# 36.net
KiCad netlist of a schematic drawn in Altium Designer
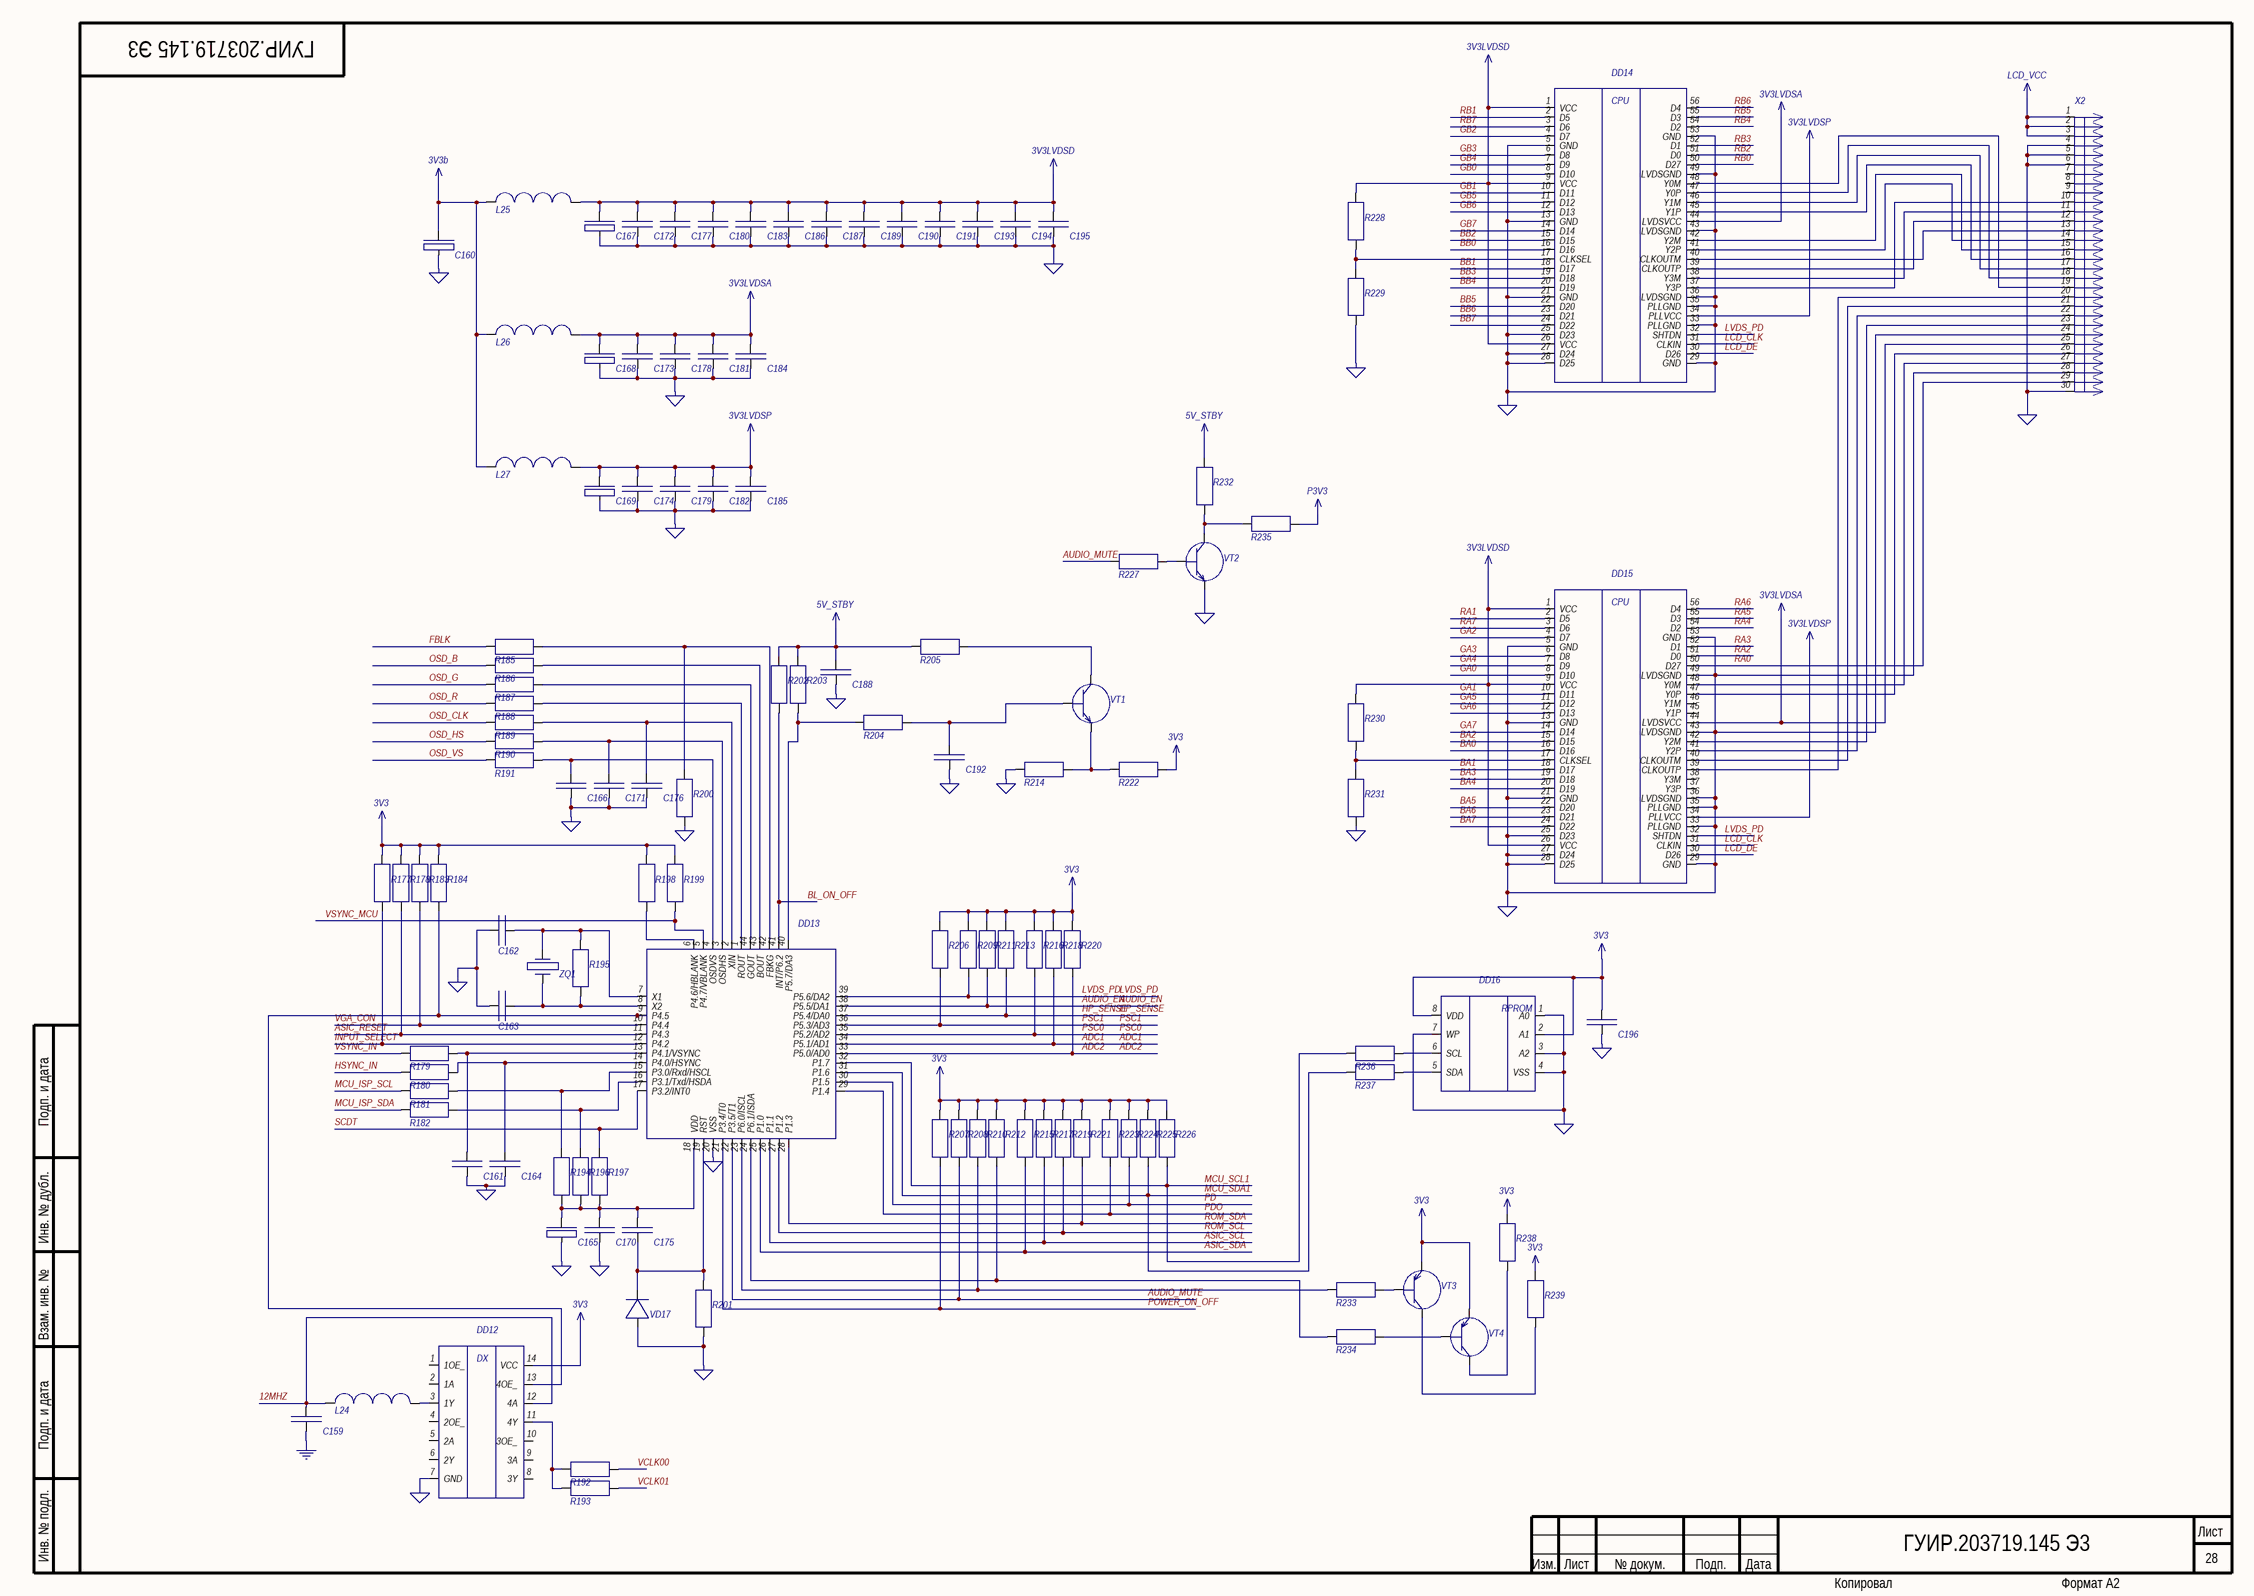
[diagram p0: 36.SchDoc]

(export (version "E")
  (design (tool "Eeschema 10.0.6"))
  (components
    (comp (ref "C159")
      (value "Capacitor")
      (footprint "cap_electro_13")
      (libsource (lib "31_lib") (part "Capacitor"))
    )
    (comp (ref "C160")
      (value "TuningCapacitor")
      (footprint "31_lib:Cap_tantal_D")
      (libsource (lib "31_lib") (part "TuningCapacitor"))
    )
    (comp (ref "C161")
      (value "Capacitor")
      (footprint "cap_electro_13")
      (libsource (lib "31_lib") (part "Capacitor"))
    )
    (comp (ref "C162")
      (value "Capacitor")
      (footprint "cap_electro_13")
      (libsource (lib "31_lib") (part "Capacitor"))
    )
    (comp (ref "C163")
      (value "Capacitor")
      (footprint "cap_electro_13")
      (libsource (lib "31_lib") (part "Capacitor"))
    )
    (comp (ref "C164")
      (value "Capacitor")
      (footprint "cap_electro_13")
      (libsource (lib "31_lib") (part "Capacitor"))
    )
    (comp (ref "C165")
      (value "TuningCapacitor")
      (footprint "31_lib:Cap_tantal_D")
      (libsource (lib "31_lib") (part "TuningCapacitor"))
    )
    (comp (ref "C166")
      (value "Capacitor")
      (footprint "cap_electro_13")
      (libsource (lib "31_lib") (part "Capacitor"))
    )
    (comp (ref "C167")
      (value "TuningCapacitor")
      (footprint "31_lib:Cap_tantal_D")
      (libsource (lib "31_lib") (part "TuningCapacitor"))
    )
    (comp (ref "C168")
      (value "TuningCapacitor")
      (footprint "31_lib:Cap_tantal_D")
      (libsource (lib "31_lib") (part "TuningCapacitor"))
    )
    (comp (ref "C169")
      (value "TuningCapacitor")
      (footprint "31_lib:Cap_tantal_D")
      (libsource (lib "31_lib") (part "TuningCapacitor"))
    )
    (comp (ref "C170")
      (value "Capacitor")
      (footprint "cap_electro_13")
      (libsource (lib "31_lib") (part "Capacitor"))
    )
    (comp (ref "C171")
      (value "Capacitor")
      (footprint "cap_electro_13")
      (libsource (lib "31_lib") (part "Capacitor"))
    )
    (comp (ref "C172")
      (value "Capacitor")
      (footprint "cap_electro_13")
      (libsource (lib "31_lib") (part "Capacitor"))
    )
    (comp (ref "C173")
      (value "Capacitor")
      (footprint "cap_electro_13")
      (libsource (lib "31_lib") (part "Capacitor"))
    )
    (comp (ref "C174")
      (value "Capacitor")
      (footprint "cap_electro_13")
      (libsource (lib "31_lib") (part "Capacitor"))
    )
    (comp (ref "C175")
      (value "Capacitor")
      (footprint "cap_electro_13")
      (libsource (lib "31_lib") (part "Capacitor"))
    )
    (comp (ref "C176")
      (value "Capacitor")
      (footprint "cap_electro_13")
      (libsource (lib "31_lib") (part "Capacitor"))
    )
    (comp (ref "C177")
      (value "Capacitor")
      (footprint "cap_electro_13")
      (libsource (lib "31_lib") (part "Capacitor"))
    )
    (comp (ref "C178")
      (value "Capacitor")
      (footprint "cap_electro_13")
      (libsource (lib "31_lib") (part "Capacitor"))
    )
    (comp (ref "C179")
      (value "Capacitor")
      (footprint "cap_electro_13")
      (libsource (lib "31_lib") (part "Capacitor"))
    )
    (comp (ref "C180")
      (value "Capacitor")
      (footprint "cap_electro_13")
      (libsource (lib "31_lib") (part "Capacitor"))
    )
    (comp (ref "C181")
      (value "Capacitor")
      (footprint "cap_electro_13")
      (libsource (lib "31_lib") (part "Capacitor"))
    )
    (comp (ref "C182")
      (value "Capacitor")
      (footprint "cap_electro_13")
      (libsource (lib "31_lib") (part "Capacitor"))
    )
    (comp (ref "C183")
      (value "Capacitor")
      (footprint "cap_electro_13")
      (libsource (lib "31_lib") (part "Capacitor"))
    )
    (comp (ref "C184")
      (value "Capacitor")
      (footprint "cap_electro_13")
      (libsource (lib "31_lib") (part "Capacitor"))
    )
    (comp (ref "C185")
      (value "Capacitor")
      (footprint "cap_electro_13")
      (libsource (lib "31_lib") (part "Capacitor"))
    )
    (comp (ref "C186")
      (value "Capacitor")
      (footprint "cap_electro_13")
      (libsource (lib "31_lib") (part "Capacitor"))
    )
    (comp (ref "C187")
      (value "Capacitor")
      (footprint "cap_electro_13")
      (libsource (lib "31_lib") (part "Capacitor"))
    )
    (comp (ref "C188")
      (value "Capacitor")
      (footprint "cap_electro_13")
      (libsource (lib "31_lib") (part "Capacitor"))
    )
    (comp (ref "C189")
      (value "Capacitor")
      (footprint "cap_electro_13")
      (libsource (lib "31_lib") (part "Capacitor"))
    )
    (comp (ref "C190")
      (value "Capacitor")
      (footprint "cap_electro_13")
      (libsource (lib "31_lib") (part "Capacitor"))
    )
    (comp (ref "C191")
      (value "Capacitor")
      (footprint "cap_electro_13")
      (libsource (lib "31_lib") (part "Capacitor"))
    )
    (comp (ref "C192")
      (value "Capacitor")
      (footprint "cap_electro_13")
      (libsource (lib "31_lib") (part "Capacitor"))
    )
    (comp (ref "C193")
      (value "Capacitor")
      (footprint "cap_electro_13")
      (libsource (lib "31_lib") (part "Capacitor"))
    )
    (comp (ref "C194")
      (value "Capacitor")
      (footprint "cap_electro_13")
      (libsource (lib "31_lib") (part "Capacitor"))
    )
    (comp (ref "C195")
      (value "Capacitor")
      (footprint "cap_electro_13")
      (libsource (lib "31_lib") (part "Capacitor"))
    )
    (comp (ref "C196")
      (value "Capacitor")
      (footprint "cap_electro_13")
      (libsource (lib "31_lib") (part "Capacitor"))
    )
    (comp (ref "DD12")
      (value "74LCX125")
      (footprint "31_lib:74LCX125(page12)")
      (libsource (lib "31_lib") (part "74LCX125"))
    )
    (comp (ref "DD13")
      (value "SM0230")
      (footprint "31_lib:SM0230")
      (libsource (lib "31_lib") (part "SM0230"))
    )
    (comp (ref "DD14")
      (value "SN75LVDS83")
      (footprint "31_lib:SN75LVDS83_v2")
      (libsource (lib "31_lib") (part "SN75LVDS83"))
    )
    (comp (ref "DD15")
      (value "SN75LVDS83")
      (footprint "31_lib:SN75LVDS83_v2")
      (libsource (lib "31_lib") (part "SN75LVDS83"))
    )
    (comp (ref "DD16") (value "24LC16") (footprint "31_lib:24Cxx") (libsource (lib "31_lib") (part "24LC16")))
    (comp (ref "L24")
      (value "Inductor")
      (footprint "31_lib:inductor")
      (libsource (lib "31_lib") (part "Inductor"))
    )
    (comp (ref "L25")
      (value "Inductor")
      (footprint "31_lib:inductor")
      (libsource (lib "31_lib") (part "Inductor"))
    )
    (comp (ref "L26")
      (value "Inductor")
      (footprint "31_lib:inductor")
      (libsource (lib "31_lib") (part "Inductor"))
    )
    (comp (ref "L27")
      (value "Inductor")
      (footprint "31_lib:inductor")
      (libsource (lib "31_lib") (part "Inductor"))
    )
    (comp (ref "R177")
      (value "Resistor")
      (footprint "lab_7_footprints:R_1206")
      (libsource (lib "31_lib") (part "Resistor"))
    )
    (comp (ref "R178")
      (value "Resistor")
      (footprint "lab_7_footprints:R_1206")
      (libsource (lib "31_lib") (part "Resistor"))
    )
    (comp (ref "R179")
      (value "Resistor")
      (footprint "lab_7_footprints:R_1206")
      (libsource (lib "31_lib") (part "Resistor"))
    )
    (comp (ref "R180")
      (value "Resistor")
      (footprint "lab_7_footprints:R_1206")
      (libsource (lib "31_lib") (part "Resistor"))
    )
    (comp (ref "R181")
      (value "Resistor")
      (footprint "lab_7_footprints:R_1206")
      (libsource (lib "31_lib") (part "Resistor"))
    )
    (comp (ref "R182")
      (value "Resistor")
      (footprint "lab_7_footprints:R_1206")
      (libsource (lib "31_lib") (part "Resistor"))
    )
    (comp (ref "R183")
      (value "Resistor")
      (footprint "lab_7_footprints:R_1206")
      (libsource (lib "31_lib") (part "Resistor"))
    )
    (comp (ref "R184")
      (value "Resistor")
      (footprint "lab_7_footprints:R_1206")
      (libsource (lib "31_lib") (part "Resistor"))
    )
    (comp (ref "R185")
      (value "Resistor")
      (footprint "lab_7_footprints:R_1206")
      (libsource (lib "31_lib") (part "Resistor"))
    )
    (comp (ref "R186")
      (value "Resistor")
      (footprint "lab_7_footprints:R_1206")
      (libsource (lib "31_lib") (part "Resistor"))
    )
    (comp (ref "R187")
      (value "Resistor")
      (footprint "lab_7_footprints:R_1206")
      (libsource (lib "31_lib") (part "Resistor"))
    )
    (comp (ref "R188")
      (value "Resistor")
      (footprint "lab_7_footprints:R_1206")
      (libsource (lib "31_lib") (part "Resistor"))
    )
    (comp (ref "R189")
      (value "Resistor")
      (footprint "lab_7_footprints:R_1206")
      (libsource (lib "31_lib") (part "Resistor"))
    )
    (comp (ref "R190")
      (value "Resistor")
      (footprint "lab_7_footprints:R_1206")
      (libsource (lib "31_lib") (part "Resistor"))
    )
    (comp (ref "R191")
      (value "Resistor")
      (footprint "lab_7_footprints:R_1206")
      (libsource (lib "31_lib") (part "Resistor"))
    )
    (comp (ref "R192")
      (value "Resistor")
      (footprint "lab_7_footprints:R_1206")
      (libsource (lib "31_lib") (part "Resistor"))
    )
    (comp (ref "R193")
      (value "Resistor")
      (footprint "lab_7_footprints:R_1206")
      (libsource (lib "31_lib") (part "Resistor"))
    )
    (comp (ref "R194")
      (value "Resistor")
      (footprint "lab_7_footprints:R_1206")
      (libsource (lib "31_lib") (part "Resistor"))
    )
    (comp (ref "R195")
      (value "Resistor")
      (footprint "lab_7_footprints:R_1206")
      (libsource (lib "31_lib") (part "Resistor"))
    )
    (comp (ref "R196")
      (value "Resistor")
      (footprint "lab_7_footprints:R_1206")
      (libsource (lib "31_lib") (part "Resistor"))
    )
    (comp (ref "R197")
      (value "Resistor")
      (footprint "lab_7_footprints:R_1206")
      (libsource (lib "31_lib") (part "Resistor"))
    )
    (comp (ref "R198")
      (value "Resistor")
      (footprint "lab_7_footprints:R_1206")
      (libsource (lib "31_lib") (part "Resistor"))
    )
    (comp (ref "R199")
      (value "Resistor")
      (footprint "lab_7_footprints:R_1206")
      (libsource (lib "31_lib") (part "Resistor"))
    )
    (comp (ref "R200")
      (value "Resistor")
      (footprint "lab_7_footprints:R_1206")
      (libsource (lib "31_lib") (part "Resistor"))
    )
    (comp (ref "R201")
      (value "Resistor")
      (footprint "lab_7_footprints:R_1206")
      (libsource (lib "31_lib") (part "Resistor"))
    )
    (comp (ref "R202")
      (value "Resistor")
      (footprint "lab_7_footprints:R_1206")
      (libsource (lib "31_lib") (part "Resistor"))
    )
    (comp (ref "R203")
      (value "Resistor")
      (footprint "lab_7_footprints:R_1206")
      (libsource (lib "31_lib") (part "Resistor"))
    )
    (comp (ref "R204")
      (value "Resistor")
      (footprint "lab_7_footprints:R_1206")
      (libsource (lib "31_lib") (part "Resistor"))
    )
    (comp (ref "R205")
      (value "Resistor")
      (footprint "lab_7_footprints:R_1206")
      (libsource (lib "31_lib") (part "Resistor"))
    )
    (comp (ref "R206")
      (value "Resistor")
      (footprint "lab_7_footprints:R_1206")
      (libsource (lib "31_lib") (part "Resistor"))
    )
    (comp (ref "R207")
      (value "Resistor")
      (footprint "lab_7_footprints:R_1206")
      (libsource (lib "31_lib") (part "Resistor"))
    )
    (comp (ref "R208")
      (value "Resistor")
      (footprint "lab_7_footprints:R_1206")
      (libsource (lib "31_lib") (part "Resistor"))
    )
    (comp (ref "R209")
      (value "Resistor")
      (footprint "lab_7_footprints:R_1206")
      (libsource (lib "31_lib") (part "Resistor"))
    )
    (comp (ref "R210")
      (value "Resistor")
      (footprint "lab_7_footprints:R_1206")
      (libsource (lib "31_lib") (part "Resistor"))
    )
    (comp (ref "R211")
      (value "Resistor")
      (footprint "lab_7_footprints:R_1206")
      (libsource (lib "31_lib") (part "Resistor"))
    )
    (comp (ref "R212")
      (value "Resistor")
      (footprint "lab_7_footprints:R_1206")
      (libsource (lib "31_lib") (part "Resistor"))
    )
    (comp (ref "R213")
      (value "Resistor")
      (footprint "lab_7_footprints:R_1206")
      (libsource (lib "31_lib") (part "Resistor"))
    )
    (comp (ref "R214")
      (value "Resistor")
      (footprint "lab_7_footprints:R_1206")
      (libsource (lib "31_lib") (part "Resistor"))
    )
    (comp (ref "R215")
      (value "Resistor")
      (footprint "lab_7_footprints:R_1206")
      (libsource (lib "31_lib") (part "Resistor"))
    )
    (comp (ref "R216")
      (value "Resistor")
      (footprint "lab_7_footprints:R_1206")
      (libsource (lib "31_lib") (part "Resistor"))
    )
    (comp (ref "R217")
      (value "Resistor")
      (footprint "lab_7_footprints:R_1206")
      (libsource (lib "31_lib") (part "Resistor"))
    )
    (comp (ref "R218")
      (value "Resistor")
      (footprint "lab_7_footprints:R_1206")
      (libsource (lib "31_lib") (part "Resistor"))
    )
    (comp (ref "R219")
      (value "Resistor")
      (footprint "lab_7_footprints:R_1206")
      (libsource (lib "31_lib") (part "Resistor"))
    )
    (comp (ref "R220")
      (value "Resistor")
      (footprint "lab_7_footprints:R_1206")
      (libsource (lib "31_lib") (part "Resistor"))
    )
    (comp (ref "R221")
      (value "Resistor")
      (footprint "lab_7_footprints:R_1206")
      (libsource (lib "31_lib") (part "Resistor"))
    )
    (comp (ref "R222")
      (value "Resistor")
      (footprint "lab_7_footprints:R_1206")
      (libsource (lib "31_lib") (part "Resistor"))
    )
    (comp (ref "R223")
      (value "Resistor")
      (footprint "lab_7_footprints:R_1206")
      (libsource (lib "31_lib") (part "Resistor"))
    )
    (comp (ref "R224")
      (value "Resistor")
      (footprint "lab_7_footprints:R_1206")
      (libsource (lib "31_lib") (part "Resistor"))
    )
    (comp (ref "R225")
      (value "Resistor")
      (footprint "lab_7_footprints:R_1206")
      (libsource (lib "31_lib") (part "Resistor"))
    )
    (comp (ref "R226")
      (value "Resistor")
      (footprint "lab_7_footprints:R_1206")
      (libsource (lib "31_lib") (part "Resistor"))
    )
    (comp (ref "R227")
      (value "Resistor")
      (footprint "lab_7_footprints:R_1206")
      (libsource (lib "31_lib") (part "Resistor"))
    )
    (comp (ref "R228")
      (value "Resistor")
      (footprint "lab_7_footprints:R_1206")
      (libsource (lib "31_lib") (part "Resistor"))
    )
    (comp (ref "R229")
      (value "Resistor")
      (footprint "lab_7_footprints:R_1206")
      (libsource (lib "31_lib") (part "Resistor"))
    )
    (comp (ref "R230")
      (value "Resistor")
      (footprint "lab_7_footprints:R_1206")
      (libsource (lib "31_lib") (part "Resistor"))
    )
    (comp (ref "R231")
      (value "Resistor")
      (footprint "lab_7_footprints:R_1206")
      (libsource (lib "31_lib") (part "Resistor"))
    )
    (comp (ref "R232")
      (value "Resistor")
      (footprint "lab_7_footprints:R_1206")
      (libsource (lib "31_lib") (part "Resistor"))
    )
    (comp (ref "R233")
      (value "Resistor")
      (footprint "lab_7_footprints:R_1206")
      (libsource (lib "31_lib") (part "Resistor"))
    )
    (comp (ref "R234")
      (value "Resistor")
      (footprint "lab_7_footprints:R_1206")
      (libsource (lib "31_lib") (part "Resistor"))
    )
    (comp (ref "R235")
      (value "Resistor")
      (footprint "lab_7_footprints:R_1206")
      (libsource (lib "31_lib") (part "Resistor"))
    )
    (comp (ref "R236")
      (value "Resistor")
      (footprint "lab_7_footprints:R_1206")
      (libsource (lib "31_lib") (part "Resistor"))
    )
    (comp (ref "R237")
      (value "Resistor")
      (footprint "lab_7_footprints:R_1206")
      (libsource (lib "31_lib") (part "Resistor"))
    )
    (comp (ref "R238")
      (value "Resistor")
      (footprint "lab_7_footprints:R_1206")
      (libsource (lib "31_lib") (part "Resistor"))
    )
    (comp (ref "R239")
      (value "Resistor")
      (footprint "lab_7_footprints:R_1206")
      (libsource (lib "31_lib") (part "Resistor"))
    )
    (comp (ref "VD17")
      (value "Diode")
      (footprint "lab_7_footprints:zener_diode")
      (libsource (lib "31_lib") (part "Diode"))
    )
    (comp (ref "VT1")
      (value "MMBT3904L")
      (footprint "31_lib:MMBT3904L")
      (libsource (lib "31_lib") (part "MMBT3904L"))
    )
    (comp (ref "VT2")
      (value "MMBT3904L")
      (footprint "31_lib:MMBT3904L")
      (libsource (lib "31_lib") (part "MMBT3904L"))
    )
    (comp (ref "VT3") (value "2N3906") (footprint "31_lib:2N3906") (libsource (lib "31_lib") (part "2N3906")))
    (comp (ref "VT4") (value "2N3906") (footprint "31_lib:2N3906") (libsource (lib "31_lib") (part "2N3906")))
    (comp (ref "X2")
      (value "FI-SE30P-HF")
      (footprint "31_lib:FI-SE30P-HF_v2")
      (libsource (lib "31_lib") (part "FI-SE30P-HF"))
    )
    (comp (ref "ZQ1")
      (value "Crystal")
      (footprint "lab_7_footprints:crystal")
      (libsource (lib "31_lib") (part "Crystal"))
    )
  )
  (nets
    (net (code "1") (name "/12MHZ") (class "Default")
      (node (ref "C159") (pin "1") (pinfunction "1_1") (pintype "passive"))
      (node (ref "DD12") (pin "12") (pinfunction "4A_12") (pintype "passive"))
      (node (ref "L24") (pin "1") (pinfunction "1_1") (pintype "passive"))
    )
    (net (code "2") (name "/ADC1") (class "Default")
      (node (ref "DD13") (pin "34") (pinfunction "P5.1/AD1_34") (pintype "passive"))
      (node (ref "R218") (pin "2") (pinfunction "2_2") (pintype "passive"))
    )
    (net (code "3") (name "/ADC2") (class "Default")
      (node (ref "DD13") (pin "33") (pinfunction "P5.0/AD0_33") (pintype "passive"))
      (node (ref "R220") (pin "2") (pinfunction "2_2") (pintype "passive"))
    )
    (net (code "4") (name "/ASIC_RESET") (class "Default")
      (node (ref "DD13") (pin "11") (pinfunction "P4.3_11") (pintype "passive"))
      (node (ref "R178") (pin "1") (pinfunction "1_1") (pintype "passive"))
    )
    (net (code "5") (name "/ASIC_SCL") (class "Default")
      (node (ref "DD13") (pin "26") (pinfunction "P1.1_26") (pintype "passive"))
      (node (ref "R217") (pin "2") (pinfunction "2_2") (pintype "passive"))
    )
    (net (code "6") (name "/ASIC_SDA") (class "Default")
      (node (ref "DD13") (pin "25") (pinfunction "P1.0_25") (pintype "passive"))
      (node (ref "R215") (pin "2") (pinfunction "2_2") (pintype "passive"))
    )
    (net (code "7") (name "/AUDIO_EN") (class "Default")
      (node (ref "DD13") (pin "38") (pinfunction "P5.5/DA1_38") (pintype "passive"))
      (node (ref "R211") (pin "2") (pinfunction "2_2") (pintype "passive"))
    )
    (net (code "8") (name "/AUDIO_MUTE") (class "Default")
      (node (ref "DD13") (pin "22") (pinfunction "P3.5/T1_22") (pintype "passive"))
      (node (ref "R208") (pin "2") (pinfunction "2_2") (pintype "passive"))
      (node (ref "R227") (pin "1") (pinfunction "1_1") (pintype "passive"))
    )
    (net (code "9") (name "/BA0") (class "Default")
      (node (ref "DD15") (pin "16") (pinfunction "D16_16") (pintype "passive"))
    )
    (net (code "10") (name "/BA1") (class "Default")
      (node (ref "DD15") (pin "18") (pinfunction "D17_18") (pintype "passive"))
    )
    (net (code "11") (name "/BA2") (class "Default")
      (node (ref "DD15") (pin "15") (pinfunction "D15_15") (pintype "passive"))
    )
    (net (code "12") (name "/BA3") (class "Default")
      (node (ref "DD15") (pin "19") (pinfunction "D18_19") (pintype "passive"))
    )
    (net (code "13") (name "/BA4") (class "Default")
      (node (ref "DD15") (pin "20") (pinfunction "D19_20") (pintype "passive"))
    )
    (net (code "14") (name "/BA5") (class "Default")
      (node (ref "DD15") (pin "22") (pinfunction "D20_22") (pintype "passive"))
    )
    (net (code "15") (name "/BA6") (class "Default")
      (node (ref "DD15") (pin "23") (pinfunction "D21_23") (pintype "passive"))
    )
    (net (code "16") (name "/BA7") (class "Default")
      (node (ref "DD15") (pin "24") (pinfunction "D22_24") (pintype "passive"))
    )
    (net (code "17") (name "/BB0") (class "Default")
      (node (ref "DD14") (pin "16") (pinfunction "D16_16") (pintype "passive"))
    )
    (net (code "18") (name "/BB1") (class "Default")
      (node (ref "DD14") (pin "18") (pinfunction "D17_18") (pintype "passive"))
    )
    (net (code "19") (name "/BB2") (class "Default")
      (node (ref "DD14") (pin "15") (pinfunction "D15_15") (pintype "passive"))
    )
    (net (code "20") (name "/BB3") (class "Default")
      (node (ref "DD14") (pin "19") (pinfunction "D18_19") (pintype "passive"))
    )
    (net (code "21") (name "/BB4") (class "Default")
      (node (ref "DD14") (pin "20") (pinfunction "D19_20") (pintype "passive"))
    )
    (net (code "22") (name "/BB5") (class "Default")
      (node (ref "DD14") (pin "22") (pinfunction "D20_22") (pintype "passive"))
    )
    (net (code "23") (name "/BB6") (class "Default")
      (node (ref "DD14") (pin "23") (pinfunction "D21_23") (pintype "passive"))
    )
    (net (code "24") (name "/BB7") (class "Default")
      (node (ref "DD14") (pin "24") (pinfunction "D22_24") (pintype "passive"))
    )
    (net (code "25") (name "/BL_ON_OFF") (class "Default")
      (node (ref "DD13") (pin "41") (pinfunction "INT/P6.2_41") (pintype "passive"))
      (node (ref "R202") (pin "2") (pinfunction "2_2") (pintype "passive"))
    )
    (net (code "26") (name "/FBLK") (class "Default")
      (node (ref "R185") (pin "2") (pinfunction "2_2") (pintype "passive"))
    )
    (net (code "27") (name "/GA0") (class "Default")
      (node (ref "DD15") (pin "8") (pinfunction "D10_8") (pintype "passive"))
    )
    (net (code "28") (name "/GA1") (class "Default")
      (node (ref "DD15") (pin "10") (pinfunction "D11_10") (pintype "passive"))
    )
    (net (code "29") (name "/GA2") (class "Default")
      (node (ref "DD15") (pin "4") (pinfunction "D7_4") (pintype "passive"))
    )
    (net (code "30") (name "/GA3") (class "Default")
      (node (ref "DD15") (pin "6") (pinfunction "D8_6") (pintype "passive"))
    )
    (net (code "31") (name "/GA4") (class "Default")
      (node (ref "DD15") (pin "7") (pinfunction "D9_7") (pintype "passive"))
    )
    (net (code "32") (name "/GA5") (class "Default")
      (node (ref "DD15") (pin "11") (pinfunction "D12_11") (pintype "passive"))
    )
    (net (code "33") (name "/GA6") (class "Default")
      (node (ref "DD15") (pin "12") (pinfunction "D13_12") (pintype "passive"))
    )
    (net (code "34") (name "/GA7") (class "Default")
      (node (ref "DD15") (pin "14") (pinfunction "D14_14") (pintype "passive"))
    )
    (net (code "35") (name "/GB0") (class "Default")
      (node (ref "DD14") (pin "8") (pinfunction "D10_8") (pintype "passive"))
    )
    (net (code "36") (name "/GB1") (class "Default")
      (node (ref "DD14") (pin "10") (pinfunction "D11_10") (pintype "passive"))
    )
    (net (code "37") (name "/GB2") (class "Default")
      (node (ref "DD14") (pin "4") (pinfunction "D7_4") (pintype "passive"))
    )
    (net (code "38") (name "/GB3") (class "Default")
      (node (ref "DD14") (pin "6") (pinfunction "D8_6") (pintype "passive"))
    )
    (net (code "39") (name "/GB4") (class "Default")
      (node (ref "DD14") (pin "7") (pinfunction "D9_7") (pintype "passive"))
    )
    (net (code "40") (name "/GB5") (class "Default")
      (node (ref "DD14") (pin "11") (pinfunction "D12_11") (pintype "passive"))
    )
    (net (code "41") (name "/GB6") (class "Default")
      (node (ref "DD14") (pin "12") (pinfunction "D13_12") (pintype "passive"))
    )
    (net (code "42") (name "/GB7") (class "Default")
      (node (ref "DD14") (pin "14") (pinfunction "D14_14") (pintype "passive"))
    )
    (net (code "43") (name "/HP_SENSE") (class "Default")
      (node (ref "DD13") (pin "37") (pinfunction "P5.4/DA0_37") (pintype "passive"))
      (node (ref "R213") (pin "2") (pinfunction "2_2") (pintype "passive"))
    )
    (net (code "44") (name "/HSYNC_IN") (class "Default")
      (node (ref "R180") (pin "1") (pinfunction "1_1") (pintype "passive"))
    )
    (net (code "45") (name "/INPUT_SELECT") (class "Default")
      (node (ref "DD13") (pin "12") (pinfunction "P4.2_12") (pintype "passive"))
      (node (ref "R177") (pin "1") (pinfunction "1_1") (pintype "passive"))
    )
    (net (code "46") (name "/LCD_CLK") (class "Default")
      (node (ref "DD14") (pin "31") (pinfunction "CLKIN_31") (pintype "passive"))
      (node (ref "DD15") (pin "31") (pinfunction "CLKIN_31") (pintype "passive"))
    )
    (net (code "47") (name "/LCD_DE") (class "Default")
      (node (ref "DD14") (pin "30") (pinfunction "D26_30") (pintype "passive"))
      (node (ref "DD15") (pin "30") (pinfunction "D26_30") (pintype "passive"))
    )
    (net (code "48") (name "/LVDS_PD") (class "Default")
      (node (ref "DD13") (pin "39") (pinfunction "P5.6/DA2_39") (pintype "passive"))
      (node (ref "DD14") (pin "32") (pinfunction "SHTDN_32") (pintype "passive"))
      (node (ref "DD15") (pin "32") (pinfunction "SHTDN_32") (pintype "passive"))
      (node (ref "R209") (pin "2") (pinfunction "2_2") (pintype "passive"))
    )
    (net (code "49") (name "/MCU_ISP_SCL") (class "Default")
      (node (ref "R181") (pin "1") (pinfunction "1_1") (pintype "passive"))
    )
    (net (code "50") (name "/MCU_ISP_SDA") (class "Default")
      (node (ref "R182") (pin "1") (pinfunction "1_1") (pintype "passive"))
    )
    (net (code "51") (name "/MCU_SCL1") (class "Default")
      (node (ref "DD13") (pin "32") (pinfunction "P1.7_32") (pintype "passive"))
      (node (ref "R226") (pin "2") (pinfunction "2_2") (pintype "passive"))
      (node (ref "R236") (pin "1") (pinfunction "1_1") (pintype "passive"))
    )
    (net (code "52") (name "/MCU_SDA1") (class "Default")
      (node (ref "DD13") (pin "31") (pinfunction "P1.6_31") (pintype "passive"))
      (node (ref "R225") (pin "2") (pinfunction "2_2") (pintype "passive"))
      (node (ref "R237") (pin "1") (pinfunction "1_1") (pintype "passive"))
    )
    (net (code "53") (name "/OSD_B") (class "Default")
      (node (ref "R186") (pin "2") (pinfunction "2_2") (pintype "passive"))
    )
    (net (code "54") (name "/OSD_CLK") (class "Default")
      (node (ref "R189") (pin "2") (pinfunction "2_2") (pintype "passive"))
    )
    (net (code "55") (name "/OSD_G") (class "Default")
      (node (ref "R187") (pin "2") (pinfunction "2_2") (pintype "passive"))
    )
    (net (code "56") (name "/OSD_HS") (class "Default")
      (node (ref "R190") (pin "2") (pinfunction "2_2") (pintype "passive"))
    )
    (net (code "57") (name "/OSD_R") (class "Default")
      (node (ref "R188") (pin "2") (pinfunction "2_2") (pintype "passive"))
    )
    (net (code "58") (name "/OSD_VS") (class "Default")
      (node (ref "R191") (pin "2") (pinfunction "2_2") (pintype "passive"))
    )
    (net (code "59") (name "/PD") (class "Default")
      (node (ref "DD13") (pin "30") (pinfunction "P1.5_30") (pintype "passive"))
      (node (ref "R224") (pin "2") (pinfunction "2_2") (pintype "passive"))
    )
    (net (code "60") (name "/PDO") (class "Default")
      (node (ref "DD13") (pin "29") (pinfunction "P1.4_29") (pintype "passive"))
      (node (ref "R223") (pin "2") (pinfunction "2_2") (pintype "passive"))
    )
    (net (code "61") (name "/POWER_ON_OFF") (class "Default")
      (node (ref "DD13") (pin "21") (pinfunction "P3.4/T0_21") (pintype "passive"))
      (node (ref "R207") (pin "2") (pinfunction "2_2") (pintype "passive"))
    )
    (net (code "62") (name "/PSC0") (class "Default")
      (node (ref "DD13") (pin "35") (pinfunction "P5.2/AD2_35") (pintype "passive"))
      (node (ref "R216") (pin "2") (pinfunction "2_2") (pintype "passive"))
    )
    (net (code "63") (name "/PSC1") (class "Default")
      (node (ref "DD13") (pin "36") (pinfunction "P5.3/AD3_36") (pintype "passive"))
      (node (ref "R206") (pin "2") (pinfunction "2_2") (pintype "passive"))
    )
    (net (code "64") (name "/RA0") (class "Default")
      (node (ref "DD15") (pin "50") (pinfunction "D27_50") (pintype "passive"))
      (node (ref "X2") (pin "29") (pinfunction "RXEIN0-_29") (pintype "passive"))
    )
    (net (code "65") (name "/RA1") (class "Default")
      (node (ref "DD15") (pin "2") (pinfunction "D5_2") (pintype "passive"))
    )
    (net (code "66") (name "/RA2") (class "Default")
      (node (ref "DD15") (pin "51") (pinfunction "D0_51") (pintype "passive"))
    )
    (net (code "67") (name "/RA3") (class "Default")
      (node (ref "DD15") (pin "52") (pinfunction "D1_52") (pintype "passive"))
    )
    (net (code "68") (name "/RA4") (class "Default")
      (node (ref "DD15") (pin "54") (pinfunction "D2_54") (pintype "passive"))
    )
    (net (code "69") (name "/RA5") (class "Default")
      (node (ref "DD15") (pin "55") (pinfunction "D3_55") (pintype "passive"))
    )
    (net (code "70") (name "/RA6") (class "Default")
      (node (ref "DD15") (pin "56") (pinfunction "D4_56") (pintype "passive"))
    )
    (net (code "71") (name "/RA7") (class "Default")
      (node (ref "DD15") (pin "3") (pinfunction "D6_3") (pintype "passive"))
    )
    (net (code "72") (name "/RB0") (class "Default")
      (node (ref "DD14") (pin "50") (pinfunction "D27_50") (pintype "passive"))
    )
    (net (code "73") (name "/RB1") (class "Default")
      (node (ref "DD14") (pin "2") (pinfunction "D5_2") (pintype "passive"))
    )
    (net (code "74") (name "/RB2") (class "Default")
      (node (ref "DD14") (pin "51") (pinfunction "D0_51") (pintype "passive"))
    )
    (net (code "75") (name "/RB3") (class "Default")
      (node (ref "DD14") (pin "52") (pinfunction "D1_52") (pintype "passive"))
    )
    (net (code "76") (name "/RB4") (class "Default")
      (node (ref "DD14") (pin "54") (pinfunction "D2_54") (pintype "passive"))
    )
    (net (code "77") (name "/RB5") (class "Default")
      (node (ref "DD14") (pin "55") (pinfunction "D3_55") (pintype "passive"))
    )
    (net (code "78") (name "/RB6") (class "Default")
      (node (ref "DD14") (pin "56") (pinfunction "D4_56") (pintype "passive"))
    )
    (net (code "79") (name "/RB7") (class "Default")
      (node (ref "DD14") (pin "3") (pinfunction "D6_3") (pintype "passive"))
    )
    (net (code "80") (name "/ROM_SCL") (class "Default")
      (node (ref "DD13") (pin "27") (pinfunction "P1.2_27") (pintype "passive"))
      (node (ref "R219") (pin "2") (pinfunction "2_2") (pintype "passive"))
    )
    (net (code "81") (name "/ROM_SDA") (class "Default")
      (node (ref "DD13") (pin "28") (pinfunction "P1.3_28") (pintype "passive"))
      (node (ref "R221") (pin "2") (pinfunction "2_2") (pintype "passive"))
    )
    (net (code "82") (name "/SCDT") (class "Default")
      (node (ref "DD13") (pin "17") (pinfunction "P3.2/INT0_17") (pintype "passive"))
      (node (ref "R197") (pin "2") (pinfunction "2_2") (pintype "passive"))
    )
    (net (code "83") (name "/VCLK00") (class "Default")
      (node (ref "R192") (pin "2") (pinfunction "2_2") (pintype "passive"))
    )
    (net (code "84") (name "/VCLK01") (class "Default")
      (node (ref "R193") (pin "2") (pinfunction "2_2") (pintype "passive"))
    )
    (net (code "85") (name "/VGA_CON") (class "Default")
      (node (ref "DD13") (pin "10") (pinfunction "P4.4_10") (pintype "passive"))
      (node (ref "R183") (pin "1") (pinfunction "1_1") (pintype "passive"))
    )
    (net (code "86") (name "/VSYNC_IN") (class "Default")
      (node (ref "R179") (pin "1") (pinfunction "1_1") (pintype "passive"))
    )
    (net (code "87") (name "/VSYNC_MCU") (class "Default")
      (node (ref "DD13") (pin "5") (pinfunction "P4.7/VBLANK_5") (pintype "passive"))
      (node (ref "R199") (pin "1") (pinfunction "1_1") (pintype "passive"))
    )
    (net (code "88") (name "3V3") (class "Default")
      (node (ref "C196") (pin "1") (pinfunction "1_1") (pintype "passive"))
      (node (ref "DD12") (pin "14") (pinfunction "VCC_14") (pintype "passive"))
      (node (ref "DD16") (pin "2") (pinfunction "A1_2") (pintype "passive"))
      (node (ref "DD16") (pin "8") (pinfunction "VDD_8") (pintype "passive"))
      (node (ref "R177") (pin "2") (pinfunction "2_2") (pintype "passive"))
      (node (ref "R178") (pin "2") (pinfunction "2_2") (pintype "passive"))
      (node (ref "R183") (pin "2") (pinfunction "2_2") (pintype "passive"))
      (node (ref "R184") (pin "2") (pinfunction "2_2") (pintype "passive"))
      (node (ref "R198") (pin "2") (pinfunction "2_2") (pintype "passive"))
      (node (ref "R199") (pin "2") (pinfunction "2_2") (pintype "passive"))
      (node (ref "R206") (pin "1") (pinfunction "1_1") (pintype "passive"))
      (node (ref "R207") (pin "1") (pinfunction "1_1") (pintype "passive"))
      (node (ref "R208") (pin "1") (pinfunction "1_1") (pintype "passive"))
      (node (ref "R209") (pin "1") (pinfunction "1_1") (pintype "passive"))
      (node (ref "R210") (pin "1") (pinfunction "1_1") (pintype "passive"))
      (node (ref "R211") (pin "1") (pinfunction "1_1") (pintype "passive"))
      (node (ref "R212") (pin "1") (pinfunction "1_1") (pintype "passive"))
      (node (ref "R213") (pin "1") (pinfunction "1_1") (pintype "passive"))
      (node (ref "R215") (pin "1") (pinfunction "1_1") (pintype "passive"))
      (node (ref "R216") (pin "1") (pinfunction "1_1") (pintype "passive"))
      (node (ref "R217") (pin "1") (pinfunction "1_1") (pintype "passive"))
      (node (ref "R218") (pin "1") (pinfunction "1_1") (pintype "passive"))
      (node (ref "R219") (pin "1") (pinfunction "1_1") (pintype "passive"))
      (node (ref "R220") (pin "1") (pinfunction "1_1") (pintype "passive"))
      (node (ref "R221") (pin "1") (pinfunction "1_1") (pintype "passive"))
      (node (ref "R222") (pin "2") (pinfunction "2_2") (pintype "passive"))
      (node (ref "R223") (pin "1") (pinfunction "1_1") (pintype "passive"))
      (node (ref "R224") (pin "1") (pinfunction "1_1") (pintype "passive"))
      (node (ref "R225") (pin "1") (pinfunction "1_1") (pintype "passive"))
      (node (ref "R226") (pin "1") (pinfunction "1_1") (pintype "passive"))
      (node (ref "R238") (pin "2") (pinfunction "2_2") (pintype "passive"))
      (node (ref "R239") (pin "2") (pinfunction "2_2") (pintype "passive"))
      (node (ref "VT3") (pin "2") (pinfunction "Emitter_2") (pintype "passive"))
      (node (ref "VT4") (pin "2") (pinfunction "Emitter_2") (pintype "passive"))
    )
    (net (code "89") (name "3V3LVDSA") (class "Default")
      (node (ref "C168") (pin "1") (pinfunction "1_1") (pintype "passive"))
      (node (ref "C173") (pin "2") (pinfunction "2_2") (pintype "passive"))
      (node (ref "C178") (pin "2") (pinfunction "2_2") (pintype "passive"))
      (node (ref "C181") (pin "2") (pinfunction "2_2") (pintype "passive"))
      (node (ref "C184") (pin "2") (pinfunction "2_2") (pintype "passive"))
      (node (ref "DD14") (pin "44") (pinfunction "LVDSVCC_44") (pintype "passive"))
      (node (ref "DD15") (pin "44") (pinfunction "LVDSVCC_44") (pintype "passive"))
      (node (ref "L26") (pin "2") (pinfunction "2_2") (pintype "passive"))
      (node (ref "X2") (pin "25") (pinfunction "RXEIN2-_25") (pintype "passive"))
    )
    (net (code "90") (name "3V3LVDSD") (class "Default")
      (node (ref "C167") (pin "1") (pinfunction "1_1") (pintype "passive"))
      (node (ref "C172") (pin "2") (pinfunction "2_2") (pintype "passive"))
      (node (ref "C177") (pin "2") (pinfunction "2_2") (pintype "passive"))
      (node (ref "C180") (pin "2") (pinfunction "2_2") (pintype "passive"))
      (node (ref "C183") (pin "2") (pinfunction "2_2") (pintype "passive"))
      (node (ref "C186") (pin "2") (pinfunction "2_2") (pintype "passive"))
      (node (ref "C187") (pin "2") (pinfunction "2_2") (pintype "passive"))
      (node (ref "C189") (pin "2") (pinfunction "2_2") (pintype "passive"))
      (node (ref "C190") (pin "2") (pinfunction "2_2") (pintype "passive"))
      (node (ref "C191") (pin "2") (pinfunction "2_2") (pintype "passive"))
      (node (ref "C193") (pin "2") (pinfunction "2_2") (pintype "passive"))
      (node (ref "C194") (pin "2") (pinfunction "2_2") (pintype "passive"))
      (node (ref "C195") (pin "2") (pinfunction "2_2") (pintype "passive"))
      (node (ref "DD14") (pin "1") (pinfunction "VCC_1") (pintype "passive"))
      (node (ref "DD14") (pin "26") (pinfunction "VCC_26") (pintype "passive"))
      (node (ref "DD14") (pin "9") (pinfunction "VCC_9") (pintype "passive"))
      (node (ref "DD15") (pin "1") (pinfunction "VCC_1") (pintype "passive"))
      (node (ref "DD15") (pin "26") (pinfunction "VCC_26") (pintype "passive"))
      (node (ref "DD15") (pin "9") (pinfunction "VCC_9") (pintype "passive"))
      (node (ref "L25") (pin "2") (pinfunction "2_2") (pintype "passive"))
      (node (ref "R228") (pin "2") (pinfunction "2_2") (pintype "passive"))
      (node (ref "R230") (pin "2") (pinfunction "2_2") (pintype "passive"))
    )
    (net (code "91") (name "3V3LVDSP") (class "Default")
      (node (ref "C169") (pin "1") (pinfunction "1_1") (pintype "passive"))
      (node (ref "C174") (pin "2") (pinfunction "2_2") (pintype "passive"))
      (node (ref "C179") (pin "2") (pinfunction "2_2") (pintype "passive"))
      (node (ref "C182") (pin "2") (pinfunction "2_2") (pintype "passive"))
      (node (ref "C185") (pin "2") (pinfunction "2_2") (pintype "passive"))
      (node (ref "DD14") (pin "34") (pinfunction "PLLVCC_34") (pintype "passive"))
      (node (ref "DD15") (pin "34") (pinfunction "PLLVCC_34") (pintype "passive"))
      (node (ref "L27") (pin "2") (pinfunction "2_2") (pintype "passive"))
    )
    (net (code "92") (name "3V3b") (class "Default")
      (node (ref "C160") (pin "1") (pinfunction "1_1") (pintype "passive"))
      (node (ref "L25") (pin "1") (pinfunction "1_1") (pintype "passive"))
      (node (ref "L26") (pin "1") (pinfunction "1_1") (pintype "passive"))
      (node (ref "L27") (pin "1") (pinfunction "1_1") (pintype "passive"))
    )
    (net (code "93") (name "5V_STBY") (class "Default")
      (node (ref "C188") (pin "1") (pinfunction "1_1") (pintype "passive"))
      (node (ref "R202") (pin "1") (pinfunction "1_1") (pintype "passive"))
      (node (ref "R203") (pin "1") (pinfunction "1_1") (pintype "passive"))
      (node (ref "R205") (pin "1") (pinfunction "1_1") (pintype "passive"))
      (node (ref "R232") (pin "2") (pinfunction "2_2") (pintype "passive"))
    )
    (net (code "94") (name "GND") (class "Default")
      (node (ref "C159") (pin "2") (pinfunction "2_2") (pintype "passive"))
      (node (ref "C160") (pin "2") (pinfunction "2_2") (pintype "passive"))
      (node (ref "C161") (pin "1") (pinfunction "1_1") (pintype "passive"))
      (node (ref "C162") (pin "2") (pinfunction "2_2") (pintype "passive"))
      (node (ref "C163") (pin "2") (pinfunction "2_2") (pintype "passive"))
      (node (ref "C164") (pin "1") (pinfunction "1_1") (pintype "passive"))
      (node (ref "C165") (pin "2") (pinfunction "2_2") (pintype "passive"))
      (node (ref "C166") (pin "2") (pinfunction "2_2") (pintype "passive"))
      (node (ref "C167") (pin "2") (pinfunction "2_2") (pintype "passive"))
      (node (ref "C168") (pin "2") (pinfunction "2_2") (pintype "passive"))
      (node (ref "C169") (pin "2") (pinfunction "2_2") (pintype "passive"))
      (node (ref "C170") (pin "1") (pinfunction "1_1") (pintype "passive"))
      (node (ref "C171") (pin "2") (pinfunction "2_2") (pintype "passive"))
      (node (ref "C172") (pin "1") (pinfunction "1_1") (pintype "passive"))
      (node (ref "C173") (pin "1") (pinfunction "1_1") (pintype "passive"))
      (node (ref "C174") (pin "1") (pinfunction "1_1") (pintype "passive"))
      (node (ref "C176") (pin "2") (pinfunction "2_2") (pintype "passive"))
      (node (ref "C177") (pin "1") (pinfunction "1_1") (pintype "passive"))
      (node (ref "C178") (pin "1") (pinfunction "1_1") (pintype "passive"))
      (node (ref "C179") (pin "1") (pinfunction "1_1") (pintype "passive"))
      (node (ref "C180") (pin "1") (pinfunction "1_1") (pintype "passive"))
      (node (ref "C181") (pin "1") (pinfunction "1_1") (pintype "passive"))
      (node (ref "C182") (pin "1") (pinfunction "1_1") (pintype "passive"))
      (node (ref "C183") (pin "1") (pinfunction "1_1") (pintype "passive"))
      (node (ref "C184") (pin "1") (pinfunction "1_1") (pintype "passive"))
      (node (ref "C185") (pin "1") (pinfunction "1_1") (pintype "passive"))
      (node (ref "C186") (pin "1") (pinfunction "1_1") (pintype "passive"))
      (node (ref "C187") (pin "1") (pinfunction "1_1") (pintype "passive"))
      (node (ref "C188") (pin "2") (pinfunction "2_2") (pintype "passive"))
      (node (ref "C189") (pin "1") (pinfunction "1_1") (pintype "passive"))
      (node (ref "C190") (pin "1") (pinfunction "1_1") (pintype "passive"))
      (node (ref "C191") (pin "1") (pinfunction "1_1") (pintype "passive"))
      (node (ref "C192") (pin "2") (pinfunction "2_2") (pintype "passive"))
      (node (ref "C193") (pin "1") (pinfunction "1_1") (pintype "passive"))
      (node (ref "C194") (pin "1") (pinfunction "1_1") (pintype "passive"))
      (node (ref "C195") (pin "1") (pinfunction "1_1") (pintype "passive"))
      (node (ref "C196") (pin "2") (pinfunction "2_2") (pintype "passive"))
      (node (ref "DD12") (pin "7") (pinfunction "GND_7") (pintype "passive"))
      (node (ref "DD13") (pin "20") (pinfunction "VSS_20") (pintype "passive"))
      (node (ref "DD14") (pin "13") (pinfunction "GND_13") (pintype "passive"))
      (node (ref "DD14") (pin "21") (pinfunction "GND_21") (pintype "passive"))
      (node (ref "DD14") (pin "25") (pinfunction "D23_25") (pintype "passive"))
      (node (ref "DD14") (pin "27") (pinfunction "D24_27") (pintype "passive"))
      (node (ref "DD14") (pin "28") (pinfunction "D25_28") (pintype "passive"))
      (node (ref "DD14") (pin "29") (pinfunction "GND_29") (pintype "passive"))
      (node (ref "DD14") (pin "33") (pinfunction "PLLGND_33") (pintype "passive"))
      (node (ref "DD14") (pin "35") (pinfunction "PLLGND_35") (pintype "passive"))
      (node (ref "DD14") (pin "36") (pinfunction "LVDSGND_36") (pintype "passive"))
      (node (ref "DD14") (pin "43") (pinfunction "LVDSGND_43") (pintype "passive"))
      (node (ref "DD14") (pin "49") (pinfunction "LVDSGND_49") (pintype "passive"))
      (node (ref "DD14") (pin "5") (pinfunction "GND_5") (pintype "passive"))
      (node (ref "DD14") (pin "53") (pinfunction "GND_53") (pintype "passive"))
      (node (ref "DD15") (pin "13") (pinfunction "GND_13") (pintype "passive"))
      (node (ref "DD15") (pin "21") (pinfunction "GND_21") (pintype "passive"))
      (node (ref "DD15") (pin "25") (pinfunction "D23_25") (pintype "passive"))
      (node (ref "DD15") (pin "27") (pinfunction "D24_27") (pintype "passive"))
      (node (ref "DD15") (pin "28") (pinfunction "D25_28") (pintype "passive"))
      (node (ref "DD15") (pin "29") (pinfunction "GND_29") (pintype "passive"))
      (node (ref "DD15") (pin "33") (pinfunction "PLLGND_33") (pintype "passive"))
      (node (ref "DD15") (pin "35") (pinfunction "PLLGND_35") (pintype "passive"))
      (node (ref "DD15") (pin "36") (pinfunction "LVDSGND_36") (pintype "passive"))
      (node (ref "DD15") (pin "43") (pinfunction "LVDSGND_43") (pintype "passive"))
      (node (ref "DD15") (pin "49") (pinfunction "LVDSGND_49") (pintype "passive"))
      (node (ref "DD15") (pin "5") (pinfunction "GND_5") (pintype "passive"))
      (node (ref "DD15") (pin "53") (pinfunction "GND_53") (pintype "passive"))
      (node (ref "DD16") (pin "1") (pinfunction "A0_1") (pintype "passive"))
      (node (ref "DD16") (pin "3") (pinfunction "A2_3") (pintype "passive"))
      (node (ref "DD16") (pin "4") (pinfunction "VSS_4") (pintype "passive"))
      (node (ref "DD16") (pin "7") (pinfunction "WP_7") (pintype "passive"))
      (node (ref "R200") (pin "1") (pinfunction "1_1") (pintype "passive"))
      (node (ref "R201") (pin "1") (pinfunction "1_1") (pintype "passive"))
      (node (ref "R214") (pin "1") (pinfunction "1_1") (pintype "passive"))
      (node (ref "R229") (pin "1") (pinfunction "1_1") (pintype "passive"))
      (node (ref "R231") (pin "1") (pinfunction "1_1") (pintype "passive"))
      (node (ref "VD17") (pin "1") (pinfunction "1_1") (pintype "passive"))
      (node (ref "VT2") (pin "2") (pinfunction "Emitter_2") (pintype "passive"))
      (node (ref "X2") (pin "24") (pinfunction "RXEIN2+_24") (pintype "passive"))
      (node (ref "X2") (pin "28") (pinfunction "RXEIN0+_28") (pintype "passive"))
      (node (ref "X2") (pin "30") (pinfunction "LVDSGND_30") (pintype "passive"))
      (node (ref "X2") (pin "4") (pinfunction "GND_4") (pintype "passive"))
      (node (ref "X2") (pin "5") (pinfunction "GND_5") (pintype "passive"))
      (node (ref "X2") (pin "6") (pinfunction "GND_6") (pintype "passive"))
    )
    (net (code "95") (name "LCD_VCC") (class "Default")
      (node (ref "X2") (pin "1") (pinfunction "VIN_1") (pintype "passive"))
      (node (ref "X2") (pin "2") (pinfunction "VIN_2") (pintype "passive"))
      (node (ref "X2") (pin "3") (pinfunction "VIN_3") (pintype "passive"))
    )
    (net (code "96") (name "Net-(DD12-1Y)") (class "Default")
      (node (ref "DD12") (pin "3") (pinfunction "1Y_3") (pintype "passive"))
      (node (ref "L24") (pin "2") (pinfunction "2_2") (pintype "passive"))
    )
    (net (code "97") (name "Net-(DD12-4OE_)") (class "Default")
      (node (ref "DD12") (pin "13") (pinfunction "4OE__13") (pintype "passive"))
      (node (ref "DD13") (pin "9") (pinfunction "P4.5_9") (pintype "passive"))
      (node (ref "R184") (pin "1") (pinfunction "1_1") (pintype "passive"))
    )
    (net (code "98") (name "Net-(DD12-4Y)") (class "Default")
      (node (ref "DD12") (pin "11") (pinfunction "4Y_11") (pintype "passive"))
      (node (ref "R192") (pin "1") (pinfunction "1_1") (pintype "passive"))
      (node (ref "R193") (pin "1") (pinfunction "1_1") (pintype "passive"))
    )
    (net (code "99") (name "Net-(DD13-BOUT)") (class "Default")
      (node (ref "DD13") (pin "43") (pinfunction "BOUT_43") (pintype "passive"))
      (node (ref "R186") (pin "1") (pinfunction "1_1") (pintype "passive"))
    )
    (net (code "100") (name "Net-(DD13-FBKG)") (class "Default")
      (node (ref "DD13") (pin "42") (pinfunction "FBKG_42") (pintype "passive"))
      (node (ref "R185") (pin "1") (pinfunction "1_1") (pintype "passive"))
      (node (ref "R200") (pin "2") (pinfunction "2_2") (pintype "passive"))
    )
    (net (code "101") (name "Net-(DD13-GOUT)") (class "Default")
      (node (ref "DD13") (pin "44") (pinfunction "GOUT_44") (pintype "passive"))
      (node (ref "R187") (pin "1") (pinfunction "1_1") (pintype "passive"))
    )
    (net (code "102") (name "Net-(DD13-OSDHS)") (class "Default")
      (node (ref "C171") (pin "1") (pinfunction "1_1") (pintype "passive"))
      (node (ref "DD13") (pin "3") (pinfunction "OSDHS_3") (pintype "passive"))
      (node (ref "R190") (pin "1") (pinfunction "1_1") (pintype "passive"))
    )
    (net (code "103") (name "Net-(DD13-OSDVS)") (class "Default")
      (node (ref "C166") (pin "1") (pinfunction "1_1") (pintype "passive"))
      (node (ref "DD13") (pin "4") (pinfunction "OSDVS_4") (pintype "passive"))
      (node (ref "R191") (pin "1") (pinfunction "1_1") (pintype "passive"))
    )
    (net (code "104") (name "Net-(DD13-P3.0{slash}Rxd{slash}HSCL)") (class "Default")
      (node (ref "DD13") (pin "15") (pinfunction "P3.0/Rxd/HSCL_15") (pintype "passive"))
      (node (ref "R181") (pin "2") (pinfunction "2_2") (pintype "passive"))
      (node (ref "R194") (pin "2") (pinfunction "2_2") (pintype "passive"))
    )
    (net (code "105") (name "Net-(DD13-P3.1{slash}Txd{slash}HSDA)") (class "Default")
      (node (ref "DD13") (pin "16") (pinfunction "P3.1/Txd/HSDA_16") (pintype "passive"))
      (node (ref "R182") (pin "2") (pinfunction "2_2") (pintype "passive"))
      (node (ref "R196") (pin "2") (pinfunction "2_2") (pintype "passive"))
    )
    (net (code "106") (name "Net-(DD13-P4.0{slash}HSYNC)") (class "Default")
      (node (ref "C164") (pin "2") (pinfunction "2_2") (pintype "passive"))
      (node (ref "DD13") (pin "14") (pinfunction "P4.0/HSYNC_14") (pintype "passive"))
      (node (ref "R180") (pin "2") (pinfunction "2_2") (pintype "passive"))
    )
    (net (code "107") (name "Net-(DD13-P4.1{slash}VSYNC)") (class "Default")
      (node (ref "C161") (pin "2") (pinfunction "2_2") (pintype "passive"))
      (node (ref "DD13") (pin "13") (pinfunction "P4.1/VSYNC_13") (pintype "passive"))
      (node (ref "R179") (pin "2") (pinfunction "2_2") (pintype "passive"))
    )
    (net (code "108") (name "Net-(DD13-P4.6{slash}HBLANK)") (class "Default")
      (node (ref "DD13") (pin "6") (pinfunction "P4.6/HBLANK_6") (pintype "passive"))
      (node (ref "R198") (pin "1") (pinfunction "1_1") (pintype "passive"))
    )
    (net (code "109") (name "Net-(DD13-P5.7{slash}DA3)") (class "Default")
      (node (ref "DD13") (pin "40") (pinfunction "P5.7/DA3_40") (pintype "passive"))
      (node (ref "R203") (pin "2") (pinfunction "2_2") (pintype "passive"))
      (node (ref "R204") (pin "1") (pinfunction "1_1") (pintype "passive"))
    )
    (net (code "110") (name "Net-(DD13-P6.0{slash}ISCL)") (class "Default")
      (node (ref "DD13") (pin "23") (pinfunction "P6.0/ISCL_23") (pintype "passive"))
      (node (ref "R210") (pin "2") (pinfunction "2_2") (pintype "passive"))
      (node (ref "R233") (pin "1") (pinfunction "1_1") (pintype "passive"))
    )
    (net (code "111") (name "Net-(DD13-P6.1{slash}ISDA)") (class "Default")
      (node (ref "DD13") (pin "24") (pinfunction "P6.1/ISDA_24") (pintype "passive"))
      (node (ref "R212") (pin "2") (pinfunction "2_2") (pintype "passive"))
      (node (ref "R234") (pin "1") (pinfunction "1_1") (pintype "passive"))
    )
    (net (code "112") (name "Net-(DD13-ROUT)") (class "Default")
      (node (ref "DD13") (pin "1") (pinfunction "ROUT_1") (pintype "passive"))
      (node (ref "R188") (pin "1") (pinfunction "1_1") (pintype "passive"))
    )
    (net (code "113") (name "Net-(DD13-RST)") (class "Default")
      (node (ref "C175") (pin "1") (pinfunction "1_1") (pintype "passive"))
      (node (ref "DD13") (pin "19") (pinfunction "RST_19") (pintype "passive"))
      (node (ref "R201") (pin "2") (pinfunction "2_2") (pintype "passive"))
      (node (ref "VD17") (pin "2") (pinfunction "2_2") (pintype "passive"))
    )
    (net (code "114") (name "Net-(DD13-VDD)") (class "Default")
      (node (ref "C165") (pin "1") (pinfunction "1_1") (pintype "passive"))
      (node (ref "C170") (pin "2") (pinfunction "2_2") (pintype "passive"))
      (node (ref "C175") (pin "2") (pinfunction "2_2") (pintype "passive"))
      (node (ref "DD13") (pin "18") (pinfunction "VDD_18") (pintype "passive"))
      (node (ref "R194") (pin "1") (pinfunction "1_1") (pintype "passive"))
      (node (ref "R196") (pin "1") (pinfunction "1_1") (pintype "passive"))
      (node (ref "R197") (pin "1") (pinfunction "1_1") (pintype "passive"))
    )
    (net (code "115") (name "Net-(DD13-X1)") (class "Default")
      (node (ref "C162") (pin "1") (pinfunction "1_1") (pintype "passive"))
      (node (ref "DD13") (pin "7") (pinfunction "X1_7") (pintype "passive"))
      (node (ref "R195") (pin "2") (pinfunction "2_2") (pintype "passive"))
      (node (ref "ZQ1") (pin "2") (pinfunction "2_2") (pintype "passive"))
    )
    (net (code "116") (name "Net-(DD13-X2)") (class "Default")
      (node (ref "C163") (pin "1") (pinfunction "1_1") (pintype "passive"))
      (node (ref "DD13") (pin "8") (pinfunction "X2_8") (pintype "passive"))
      (node (ref "R195") (pin "1") (pinfunction "1_1") (pintype "passive"))
      (node (ref "ZQ1") (pin "1") (pinfunction "1_1") (pintype "passive"))
    )
    (net (code "117") (name "Net-(DD13-XIN)") (class "Default")
      (node (ref "C176") (pin "1") (pinfunction "1_1") (pintype "passive"))
      (node (ref "DD13") (pin "2") (pinfunction "XIN_2") (pintype "passive"))
      (node (ref "R189") (pin "1") (pinfunction "1_1") (pintype "passive"))
    )
    (net (code "118") (name "Net-(DD14-CLKOUTM)") (class "Default")
      (node (ref "DD14") (pin "40") (pinfunction "CLKOUTM_40") (pintype "passive"))
      (node (ref "X2") (pin "13") (pinfunction "RXOCLKIN-_13") (pintype "passive"))
    )
    (net (code "119") (name "Net-(DD14-CLKOUTP)") (class "Default")
      (node (ref "DD14") (pin "39") (pinfunction "CLKOUTP_39") (pintype "passive"))
      (node (ref "X2") (pin "12") (pinfunction "RXOCLKIN+_12") (pintype "passive"))
    )
    (net (code "120") (name "Net-(DD14-CLKSEL)") (class "Default")
      (node (ref "DD14") (pin "17") (pinfunction "CLKSEL_17") (pintype "passive"))
      (node (ref "R228") (pin "1") (pinfunction "1_1") (pintype "passive"))
      (node (ref "R229") (pin "2") (pinfunction "2_2") (pintype "passive"))
    )
    (net (code "121") (name "Net-(DD14-Y0M)") (class "Default")
      (node (ref "DD14") (pin "48") (pinfunction "Y0M_48") (pintype "passive"))
      (node (ref "X2") (pin "19") (pinfunction "RXOIN0-_19") (pintype "passive"))
    )
    (net (code "122") (name "Net-(DD14-Y0P)") (class "Default")
      (node (ref "DD14") (pin "47") (pinfunction "Y0P_47") (pintype "passive"))
      (node (ref "X2") (pin "18") (pinfunction "RXOIN0+_18") (pintype "passive"))
    )
    (net (code "123") (name "Net-(DD14-Y1M)") (class "Default")
      (node (ref "DD14") (pin "46") (pinfunction "Y1M_46") (pintype "passive"))
      (node (ref "X2") (pin "17") (pinfunction "RXOIN1-_17") (pintype "passive"))
    )
    (net (code "124") (name "Net-(DD14-Y1P)") (class "Default")
      (node (ref "DD14") (pin "45") (pinfunction "Y1P_45") (pintype "passive"))
      (node (ref "X2") (pin "16") (pinfunction "RXOIN1+_16") (pintype "passive"))
    )
    (net (code "125") (name "Net-(DD14-Y2M)") (class "Default")
      (node (ref "DD14") (pin "42") (pinfunction "Y2M_42") (pintype "passive"))
      (node (ref "X2") (pin "15") (pinfunction "RXOIN2-_15") (pintype "passive"))
    )
    (net (code "126") (name "Net-(DD14-Y2P)") (class "Default")
      (node (ref "DD14") (pin "41") (pinfunction "Y2P_41") (pintype "passive"))
      (node (ref "X2") (pin "14") (pinfunction "RXOIN2+_14") (pintype "passive"))
    )
    (net (code "127") (name "Net-(DD14-Y3M)") (class "Default")
      (node (ref "DD14") (pin "38") (pinfunction "Y3M_38") (pintype "passive"))
      (node (ref "X2") (pin "11") (pinfunction "RXOIN3-_11") (pintype "passive"))
    )
    (net (code "128") (name "Net-(DD14-Y3P)") (class "Default")
      (node (ref "DD14") (pin "37") (pinfunction "Y3P_37") (pintype "passive"))
      (node (ref "X2") (pin "10") (pinfunction "RXOIN3+_10") (pintype "passive"))
    )
    (net (code "129") (name "Net-(DD15-CLKOUTM)") (class "Default")
      (node (ref "DD15") (pin "40") (pinfunction "CLKOUTM_40") (pintype "passive"))
      (node (ref "X2") (pin "21") (pinfunction "RXEIN3-_21") (pintype "passive"))
    )
    (net (code "130") (name "Net-(DD15-CLKOUTP)") (class "Default")
      (node (ref "DD15") (pin "39") (pinfunction "CLKOUTP_39") (pintype "passive"))
      (node (ref "X2") (pin "20") (pinfunction "RXEIN3+_20") (pintype "passive"))
    )
    (net (code "131") (name "Net-(DD15-CLKSEL)") (class "Default")
      (node (ref "DD15") (pin "17") (pinfunction "CLKSEL_17") (pintype "passive"))
      (node (ref "R230") (pin "1") (pinfunction "1_1") (pintype "passive"))
      (node (ref "R231") (pin "2") (pinfunction "2_2") (pintype "passive"))
    )
    (net (code "132") (name "Net-(DD15-Y0M)") (class "Default")
      (node (ref "DD15") (pin "48") (pinfunction "Y0M_48") (pintype "passive"))
      (node (ref "X2") (pin "27") (pinfunction "RXEIN1-_27") (pintype "passive"))
    )
    (net (code "133") (name "Net-(DD15-Y0P)") (class "Default")
      (node (ref "DD15") (pin "47") (pinfunction "Y0P_47") (pintype "passive"))
      (node (ref "X2") (pin "26") (pinfunction "RXEIN1+_26") (pintype "passive"))
    )
    (net (code "134") (name "Net-(DD15-Y2M)") (class "Default")
      (node (ref "DD15") (pin "42") (pinfunction "Y2M_42") (pintype "passive"))
      (node (ref "X2") (pin "23") (pinfunction "RXECLKIN-_23") (pintype "passive"))
    )
    (net (code "135") (name "Net-(DD15-Y2P)") (class "Default")
      (node (ref "DD15") (pin "41") (pinfunction "Y2P_41") (pintype "passive"))
      (node (ref "X2") (pin "22") (pinfunction "RXECLKIN+_22") (pintype "passive"))
    )
    (net (code "136") (name "Net-(DD16-SCL)") (class "Default")
      (node (ref "DD16") (pin "6") (pinfunction "SCL_6") (pintype "passive"))
      (node (ref "R236") (pin "2") (pinfunction "2_2") (pintype "passive"))
    )
    (net (code "137") (name "Net-(DD16-SDA)") (class "Default")
      (node (ref "DD16") (pin "5") (pinfunction "SDA_5") (pintype "passive"))
      (node (ref "R237") (pin "2") (pinfunction "2_2") (pintype "passive"))
    )
    (net (code "138") (name "Net-(VT1-Base)") (class "Default")
      (node (ref "C192") (pin "1") (pinfunction "1_1") (pintype "passive"))
      (node (ref "R204") (pin "2") (pinfunction "2_2") (pintype "passive"))
      (node (ref "VT1") (pin "1") (pinfunction "Base_1") (pintype "passive"))
    )
    (net (code "139") (name "Net-(VT1-Collector)") (class "Default")
      (node (ref "R205") (pin "2") (pinfunction "2_2") (pintype "passive"))
      (node (ref "VT1") (pin "3") (pinfunction "Collector_3") (pintype "passive"))
    )
    (net (code "140") (name "Net-(VT1-Emitter)") (class "Default")
      (node (ref "R214") (pin "2") (pinfunction "2_2") (pintype "passive"))
      (node (ref "R222") (pin "1") (pinfunction "1_1") (pintype "passive"))
      (node (ref "VT1") (pin "2") (pinfunction "Emitter_2") (pintype "passive"))
    )
    (net (code "141") (name "Net-(VT2-Base)") (class "Default")
      (node (ref "R227") (pin "2") (pinfunction "2_2") (pintype "passive"))
      (node (ref "VT2") (pin "1") (pinfunction "Base_1") (pintype "passive"))
    )
    (net (code "142") (name "Net-(VT2-Collector)") (class "Default")
      (node (ref "R232") (pin "1") (pinfunction "1_1") (pintype "passive"))
      (node (ref "R235") (pin "1") (pinfunction "1_1") (pintype "passive"))
      (node (ref "VT2") (pin "3") (pinfunction "Collector_3") (pintype "passive"))
    )
    (net (code "143") (name "Net-(VT3-Base)") (class "Default")
      (node (ref "R233") (pin "2") (pinfunction "2_2") (pintype "passive"))
      (node (ref "VT3") (pin "1") (pinfunction "Base_1") (pintype "passive"))
    )
    (net (code "144") (name "Net-(VT3-Collector)") (class "Default")
      (node (ref "R239") (pin "1") (pinfunction "1_1") (pintype "passive"))
      (node (ref "VT3") (pin "3") (pinfunction "Collector_3") (pintype "passive"))
    )
    (net (code "145") (name "Net-(VT4-Base)") (class "Default")
      (node (ref "R234") (pin "2") (pinfunction "2_2") (pintype "passive"))
      (node (ref "VT4") (pin "1") (pinfunction "Base_1") (pintype "passive"))
    )
    (net (code "146") (name "Net-(VT4-Collector)") (class "Default")
      (node (ref "R238") (pin "1") (pinfunction "1_1") (pintype "passive"))
      (node (ref "VT4") (pin "3") (pinfunction "Collector_3") (pintype "passive"))
    )
    (net (code "147") (name "P3V3") (class "Default")
      (node (ref "R235") (pin "2") (pinfunction "2_2") (pintype "passive"))
    )
    (net (code "148") (name "unconnected-(DD12-1A-Pad2)") (class "Default")
      (node (ref "DD12") (pin "2") (pinfunction "1A_2") (pintype "passive"))
    )
    (net (code "149") (name "unconnected-(DD12-1OE_-Pad1)") (class "Default")
      (node (ref "DD12") (pin "1") (pinfunction "1OE__1") (pintype "passive"))
    )
    (net (code "150") (name "unconnected-(DD12-2A-Pad5)") (class "Default")
      (node (ref "DD12") (pin "5") (pinfunction "2A_5") (pintype "passive"))
    )
    (net (code "151") (name "unconnected-(DD12-2OE_-Pad4)") (class "Default")
      (node (ref "DD12") (pin "4") (pinfunction "2OE__4") (pintype "passive"))
    )
    (net (code "152") (name "unconnected-(DD12-2Y-Pad6)") (class "Default")
      (node (ref "DD12") (pin "6") (pinfunction "2Y_6") (pintype "passive"))
    )
    (net (code "153") (name "unconnected-(DD12-3A-Pad9)") (class "Default")
      (node (ref "DD12") (pin "9") (pinfunction "3A_9") (pintype "passive"))
    )
    (net (code "154") (name "unconnected-(DD12-3OE_-Pad10)") (class "Default")
      (node (ref "DD12") (pin "10") (pinfunction "3OE__10") (pintype "passive"))
    )
    (net (code "155") (name "unconnected-(DD12-3Y-Pad8)") (class "Default")
      (node (ref "DD12") (pin "8") (pinfunction "3Y_8") (pintype "passive"))
    )
    (net (code "156") (name "unconnected-(DD15-Y1M-Pad46)") (class "Default")
      (node (ref "DD15") (pin "46") (pinfunction "Y1M_46") (pintype "passive"))
    )
    (net (code "157") (name "unconnected-(DD15-Y1P-Pad45)") (class "Default")
      (node (ref "DD15") (pin "45") (pinfunction "Y1P_45") (pintype "passive"))
    )
    (net (code "158") (name "unconnected-(DD15-Y3M-Pad38)") (class "Default")
      (node (ref "DD15") (pin "38") (pinfunction "Y3M_38") (pintype "passive"))
    )
    (net (code "159") (name "unconnected-(DD15-Y3P-Pad37)") (class "Default")
      (node (ref "DD15") (pin "37") (pinfunction "Y3P_37") (pintype "passive"))
    )
    (net (code "160") (name "unconnected-(X2-DGND-Pad9)") (class "Default")
      (node (ref "X2") (pin "9") (pinfunction "DGND_9") (pintype "passive"))
    )
    (net (code "161") (name "unconnected-(X2-SELLVDS-Pad7)") (class "Default")
      (node (ref "X2") (pin "7") (pinfunction "SELLVDS_7") (pintype "passive"))
    )
    (net (code "162") (name "unconnected-(X2-VcontIN-Pad8)") (class "Default")
      (node (ref "X2") (pin "8") (pinfunction "VcontIN_8") (pintype "passive"))
    )
  )
)
